# IO.net
KiCad netlist of a schematic drawn in Altium Designer
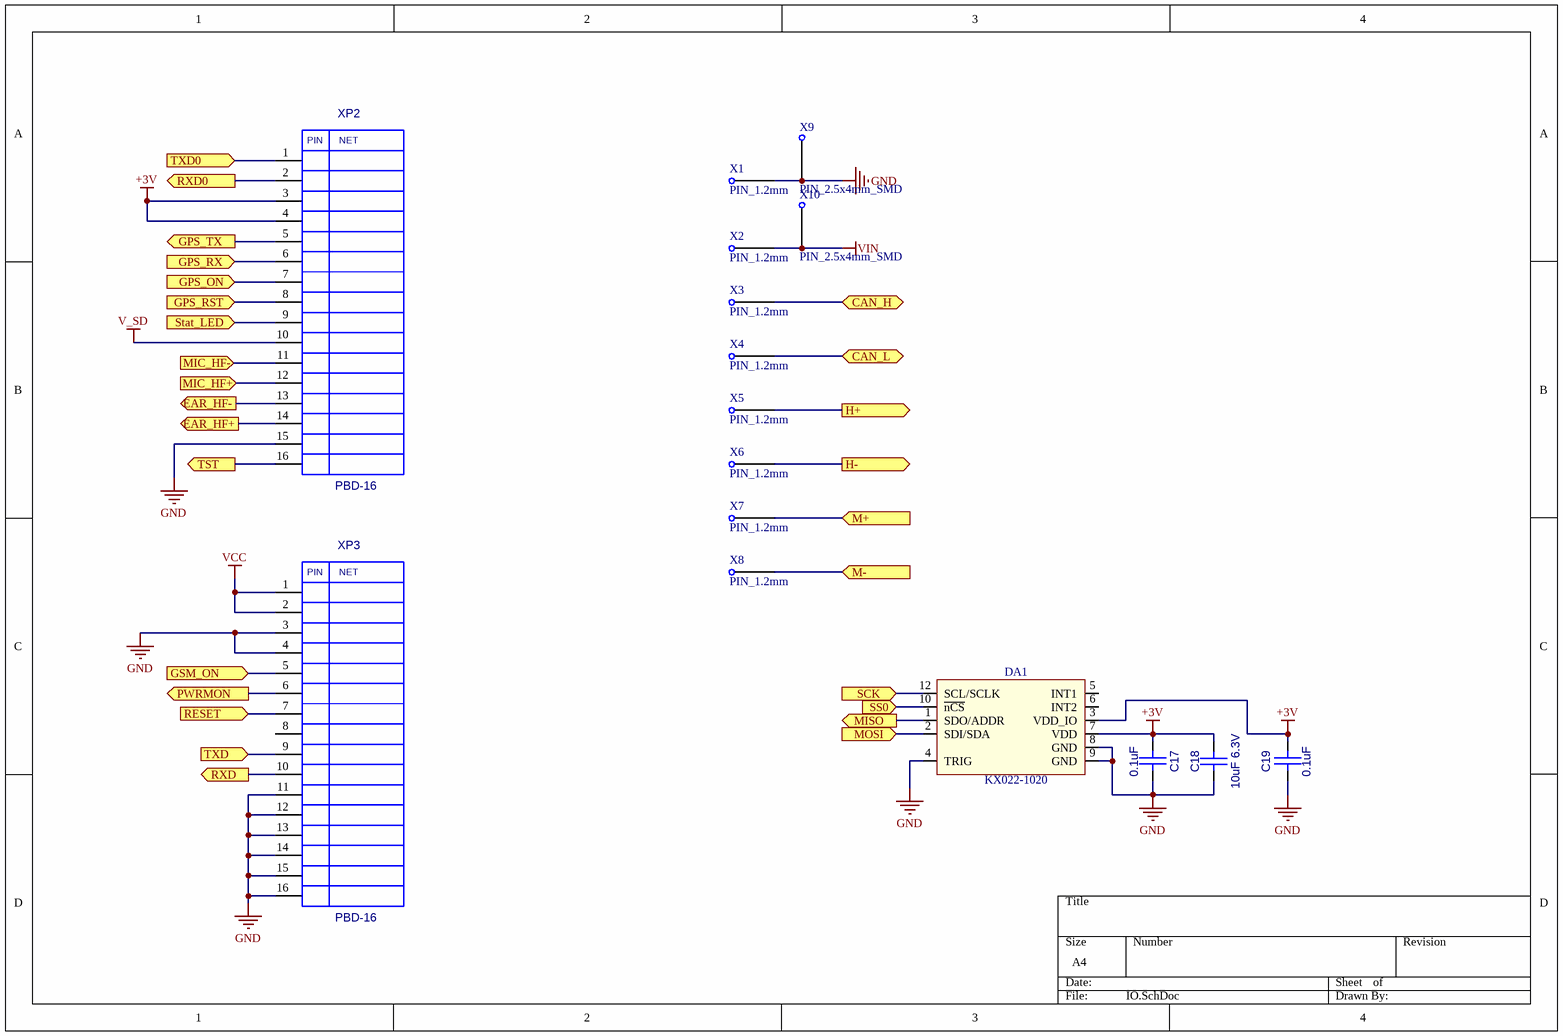
[diagram p0: IO.SchDoc]

(export (version "E")
  (design (tool "Eeschema 10.0.6"))
  (components
    (comp (ref "C17")
      (value "0.1uF")
      (footprint "CC0603")
      (description "CC0603")
      (libsource (lib "gprs_modem_2") (part "CC0603"))
    )
    (comp (ref "C18")
      (value "10uF 6.3V")
      (footprint "CC0805")
      (description "CC0805")
      (libsource (lib "gprs_modem_2") (part "CC0805"))
    )
    (comp (ref "C19")
      (value "0.1uF")
      (footprint "CC0603")
      (description "CC0603")
      (libsource (lib "gprs_modem_2") (part "CC0603"))
    )
    (comp (ref "DA1")
      (value "KX022-1020")
      (footprint "LGA-12")
      (libsource (lib "gprs_modem_2") (part "KX022-1020"))
    )
    (comp (ref "X1")
      (value "PIN_1.2mm")
      (footprint "PIN_1.2mm")
      (libsource (lib "gprs_modem_2") (part "PIN_1.2mm"))
    )
    (comp (ref "X2")
      (value "PIN_1.2mm")
      (footprint "PIN_1.2mm")
      (libsource (lib "gprs_modem_2") (part "PIN_1.2mm"))
    )
    (comp (ref "X3")
      (value "PIN_1.2mm")
      (footprint "PIN_1.2mm")
      (libsource (lib "gprs_modem_2") (part "PIN_1.2mm"))
    )
    (comp (ref "X4")
      (value "PIN_1.2mm")
      (footprint "PIN_1.2mm")
      (libsource (lib "gprs_modem_2") (part "PIN_1.2mm"))
    )
    (comp (ref "X5")
      (value "PIN_1.2mm")
      (footprint "PIN_1.2mm")
      (libsource (lib "gprs_modem_2") (part "PIN_1.2mm"))
    )
    (comp (ref "X6")
      (value "PIN_1.2mm")
      (footprint "PIN_1.2mm")
      (libsource (lib "gprs_modem_2") (part "PIN_1.2mm"))
    )
    (comp (ref "X7")
      (value "PIN_1.2mm")
      (footprint "PIN_1.2mm")
      (libsource (lib "gprs_modem_2") (part "PIN_1.2mm"))
    )
    (comp (ref "X8")
      (value "PIN_1.2mm")
      (footprint "PIN_1.2mm")
      (libsource (lib "gprs_modem_2") (part "PIN_1.2mm"))
    )
    (comp (ref "X9")
      (value "PIN_2.5x4mm_SMD")
      (footprint "PIN_2.5x4mm_SMD")
      (libsource (lib "gprs_modem_2") (part "PIN_2.5x4mm_SMD"))
    )
    (comp (ref "X10")
      (value "PIN_2.5x4mm_SMD")
      (footprint "PIN_2.5x4mm_SMD")
      (libsource (lib "gprs_modem_2") (part "PIN_2.5x4mm_SMD"))
    )
    (comp (ref "XP2") (value "PBD-16") (footprint "PBD16") (libsource (lib "gprs_modem") (part "PBD-16")))
    (comp (ref "XP3") (value "PBD-16") (footprint "PBD16") (libsource (lib "gprs_modem") (part "PBD-16")))
  )
  (nets
    (net (code "1") (name "+3V") (class "Default")
      (node (ref "C17") (pin "1") (pinfunction "A_1") (pintype "passive"))
      (node (ref "C18") (pin "2") (pinfunction "B_2") (pintype "passive"))
      (node (ref "C19") (pin "1") (pinfunction "A_1") (pintype "passive"))
      (node (ref "DA1") (pin "3") (pinfunction "VDD_IO_3") (pintype "passive"))
      (node (ref "DA1") (pin "7") (pinfunction "VDD_7") (pintype "passive"))
      (node (ref "XP2") (pin "3") (pinfunction "3_3") (pintype "passive"))
      (node (ref "XP2") (pin "4") (pinfunction "4_4") (pintype "passive"))
    )
    (net (code "2") (name "/CAN_H") (class "Default")
      (node (ref "X3") (pin "1") (pinfunction "1_1") (pintype "passive"))
    )
    (net (code "3") (name "/CAN_L") (class "Default")
      (node (ref "X4") (pin "1") (pinfunction "1_1") (pintype "passive"))
    )
    (net (code "4") (name "/EAR_HF+") (class "Default")
      (node (ref "XP2") (pin "14") (pinfunction "14_14") (pintype "passive"))
    )
    (net (code "5") (name "/EAR_HF-") (class "Default")
      (node (ref "XP2") (pin "13") (pinfunction "13_13") (pintype "passive"))
    )
    (net (code "6") (name "/GPS_ON") (class "Default")
      (node (ref "XP2") (pin "7") (pinfunction "7_7") (pintype "passive"))
    )
    (net (code "7") (name "/GPS_RST") (class "Default")
      (node (ref "XP2") (pin "8") (pinfunction "8_8") (pintype "passive"))
    )
    (net (code "8") (name "/GPS_RX") (class "Default")
      (node (ref "XP2") (pin "6") (pinfunction "6_6") (pintype "passive"))
    )
    (net (code "9") (name "/GPS_TX") (class "Default")
      (node (ref "XP2") (pin "5") (pinfunction "5_5") (pintype "passive"))
    )
    (net (code "10") (name "/GSM_ON") (class "Default")
      (node (ref "XP3") (pin "5") (pinfunction "5_5") (pintype "passive"))
    )
    (net (code "11") (name "/H+") (class "Default")
      (node (ref "X5") (pin "1") (pinfunction "1_1") (pintype "passive"))
    )
    (net (code "12") (name "/H-") (class "Default")
      (node (ref "X6") (pin "1") (pinfunction "1_1") (pintype "passive"))
    )
    (net (code "13") (name "/M+") (class "Default")
      (node (ref "X7") (pin "1") (pinfunction "1_1") (pintype "passive"))
    )
    (net (code "14") (name "/M-") (class "Default")
      (node (ref "X8") (pin "1") (pinfunction "1_1") (pintype "passive"))
    )
    (net (code "15") (name "/MIC_HF+") (class "Default")
      (node (ref "XP2") (pin "12") (pinfunction "12_12") (pintype "passive"))
    )
    (net (code "16") (name "/MIC_HF-") (class "Default")
      (node (ref "XP2") (pin "11") (pinfunction "11_11") (pintype "passive"))
    )
    (net (code "17") (name "/MISO") (class "Default")
      (node (ref "DA1") (pin "1") (pinfunction "SDO/ADDR_1") (pintype "passive"))
    )
    (net (code "18") (name "/MOSI") (class "Default")
      (node (ref "DA1") (pin "2") (pinfunction "SDI/SDA_2") (pintype "passive"))
    )
    (net (code "19") (name "/PWRMON") (class "Default")
      (node (ref "XP3") (pin "6") (pinfunction "6_6") (pintype "passive"))
    )
    (net (code "20") (name "/RESET") (class "Default")
      (node (ref "XP3") (pin "7") (pinfunction "7_7") (pintype "passive"))
    )
    (net (code "21") (name "/RXD") (class "Default")
      (node (ref "XP3") (pin "10") (pinfunction "10_10") (pintype "passive"))
    )
    (net (code "22") (name "/RXD0") (class "Default")
      (node (ref "XP2") (pin "2") (pinfunction "2_2") (pintype "passive"))
    )
    (net (code "23") (name "/SCK") (class "Default")
      (node (ref "DA1") (pin "12") (pinfunction "SCL/SCLK_12") (pintype "passive"))
    )
    (net (code "24") (name "/SS0") (class "Default")
      (node (ref "DA1") (pin "10") (pinfunction "~{nCS}_10") (pintype "passive"))
    )
    (net (code "25") (name "/Stat_LED") (class "Default")
      (node (ref "XP2") (pin "9") (pinfunction "9_9") (pintype "passive"))
    )
    (net (code "26") (name "/TST") (class "Default")
      (node (ref "XP2") (pin "16") (pinfunction "16_16") (pintype "passive"))
    )
    (net (code "27") (name "/TXD") (class "Default")
      (node (ref "XP3") (pin "9") (pinfunction "9_9") (pintype "passive"))
    )
    (net (code "28") (name "/TXD0") (class "Default")
      (node (ref "XP2") (pin "1") (pinfunction "1_1") (pintype "passive"))
    )
    (net (code "29") (name "GND") (class "Default")
      (node (ref "C17") (pin "2") (pinfunction "B_2") (pintype "passive"))
      (node (ref "C18") (pin "1") (pinfunction "A_1") (pintype "passive"))
      (node (ref "C19") (pin "2") (pinfunction "B_2") (pintype "passive"))
      (node (ref "DA1") (pin "4") (pinfunction "TRIG_4") (pintype "passive"))
      (node (ref "DA1") (pin "8") (pinfunction "GND_8") (pintype "passive"))
      (node (ref "DA1") (pin "9") (pinfunction "GND_9") (pintype "passive"))
      (node (ref "X1") (pin "1") (pinfunction "1_1") (pintype "passive"))
      (node (ref "X9") (pin "1") (pinfunction "1_1") (pintype "passive"))
      (node (ref "XP2") (pin "15") (pinfunction "15_15") (pintype "passive"))
      (node (ref "XP3") (pin "11") (pinfunction "11_11") (pintype "passive"))
      (node (ref "XP3") (pin "12") (pinfunction "12_12") (pintype "passive"))
      (node (ref "XP3") (pin "13") (pinfunction "13_13") (pintype "passive"))
      (node (ref "XP3") (pin "14") (pinfunction "14_14") (pintype "passive"))
      (node (ref "XP3") (pin "15") (pinfunction "15_15") (pintype "passive"))
      (node (ref "XP3") (pin "16") (pinfunction "16_16") (pintype "passive"))
      (node (ref "XP3") (pin "3") (pinfunction "3_3") (pintype "passive"))
      (node (ref "XP3") (pin "4") (pinfunction "4_4") (pintype "passive"))
    )
    (net (code "30") (name "VCC") (class "Default")
      (node (ref "XP3") (pin "1") (pinfunction "1_1") (pintype "passive"))
      (node (ref "XP3") (pin "2") (pinfunction "2_2") (pintype "passive"))
    )
    (net (code "31") (name "VIN") (class "Default")
      (node (ref "X10") (pin "1") (pinfunction "1_1") (pintype "passive"))
      (node (ref "X2") (pin "1") (pinfunction "1_1") (pintype "passive"))
    )
    (net (code "32") (name "V_SD") (class "Default")
      (node (ref "XP2") (pin "10") (pinfunction "10_10") (pintype "passive"))
    )
    (net (code "33") (name "unconnected-(DA1-INT1-Pad5)") (class "Default")
      (node (ref "DA1") (pin "5") (pinfunction "INT1_5") (pintype "passive"))
    )
    (net (code "34") (name "unconnected-(DA1-INT2-Pad6)") (class "Default")
      (node (ref "DA1") (pin "6") (pinfunction "INT2_6") (pintype "passive"))
    )
    (net (code "35") (name "unconnected-(XP3-Pad8)") (class "Default")
      (node (ref "XP3") (pin "8") (pinfunction "8_8") (pintype "passive"))
    )
  )
)
